# converter.net
KiCad netlist of a schematic drawn in EAGLE
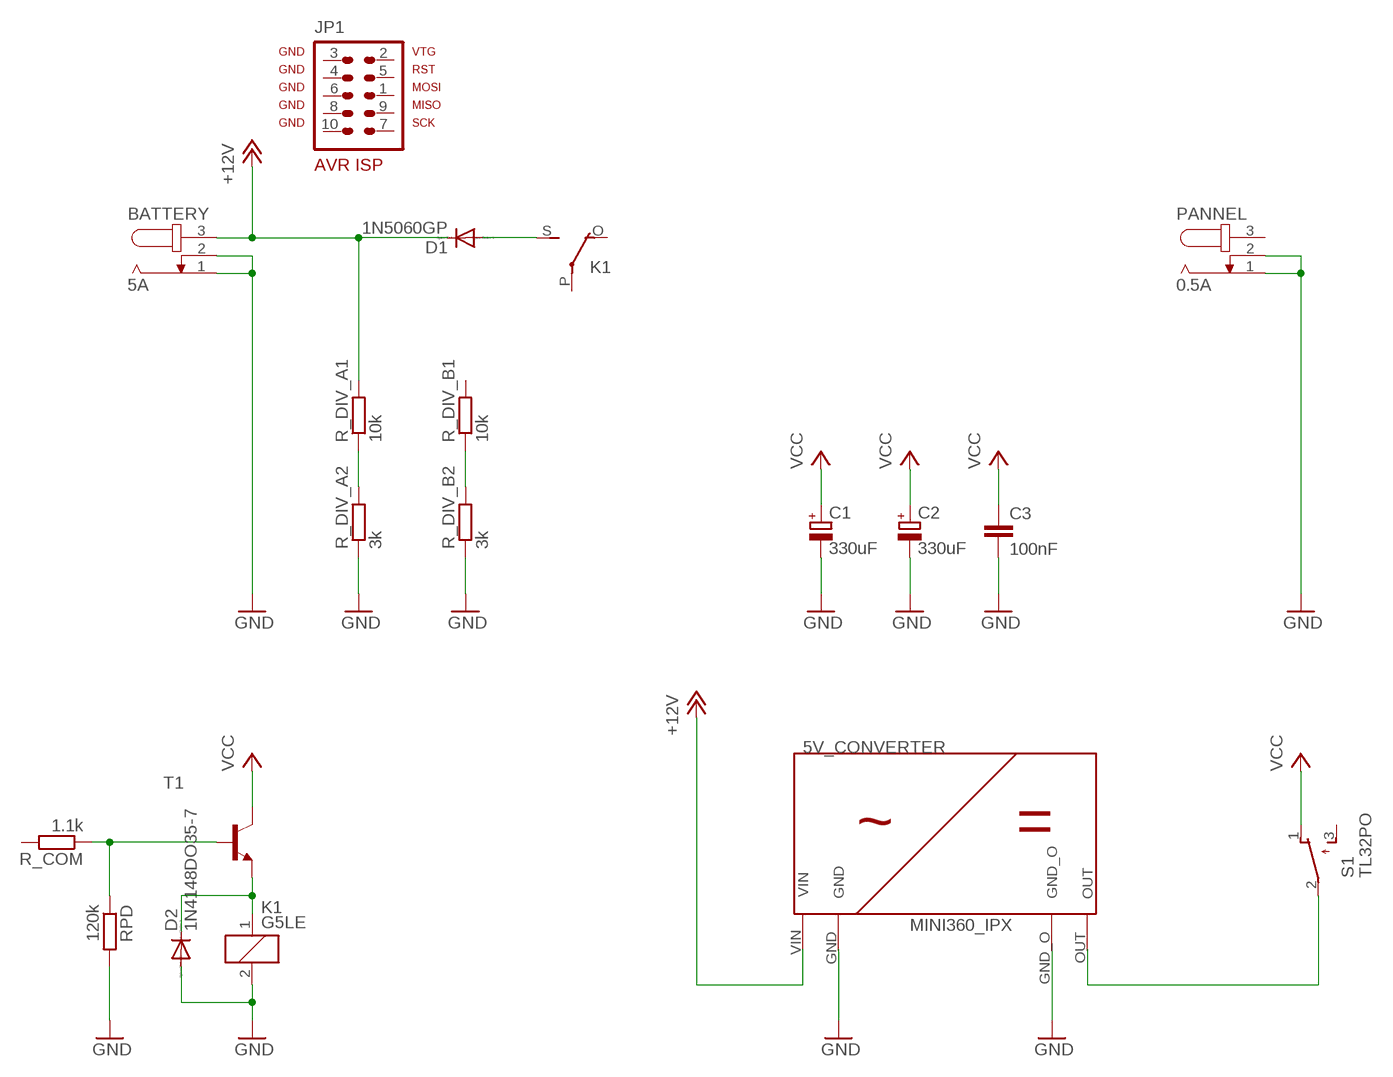
[diagram p0: schematic, sheet 1]

(export (version "E")
  (design (tool "Eeschema 10.0.6"))
  (components
    (comp (ref "5V_CONVERTER")
      (value "MINI360_IPX")
      (footprint "eagle-import:MINI360_IPX")
      (libsource (lib "eagle-import") (part "MINI360_IPX"))
    )
    (comp (ref "BATTERY")
      (value "5A")
      (footprint "eagle-import:SPC4077")
      (libsource (lib "eagle-import") (part "JACK-PLUG0"))
    )
    (comp (ref "C1")
      (value "330uF")
      (footprint "eagle-import:E2,5-7")
      (libsource (lib "eagle-import") (part "CPOL-EUE2.5-7"))
    )
    (comp (ref "C2")
      (value "330uF")
      (footprint "eagle-import:E2,5-7")
      (libsource (lib "eagle-import") (part "CPOL-EUE2.5-7"))
    )
    (comp (ref "C3")
      (value "100nF")
      (footprint "eagle-import:C025-030X050")
      (libsource (lib "eagle-import") (part "C-EU025-030X050"))
    )
    (comp (ref "D1")
      (value "1N5060GP")
      (footprint "eagle-import:DO15-12")
      (libsource (lib "eagle-import") (part "1N5060GP"))
    )
    (comp (ref "D2")
      (value "1N4148DO35-7")
      (footprint "eagle-import:DO35-7")
      (libsource (lib "eagle-import") (part "1N4148DO35-7"))
    )
    (comp (ref "JP1")
      (value "AVR-ISP-10")
      (footprint "eagle-import:AVR-ISP-10")
      (libsource (lib "eagle-import") (part "AVR-ISP-10"))
    )
    (comp (ref "K1")
      (value "G5LE")
      (footprint "eagle-import:G5LE")
      (libsource (lib "eagle-import") (part "G5LE"))
    )
    (comp (ref "PANNEL")
      (value "0.5A")
      (footprint "eagle-import:SPC4077")
      (libsource (lib "eagle-import") (part "JACK-PLUG0"))
    )
    (comp (ref "RPD")
      (value "120k")
      (footprint "eagle-import:0207_10")
      (libsource (lib "eagle-import") (part "R-EU_0207/10"))
    )
    (comp (ref "R_COM")
      (value "1.1k")
      (footprint "eagle-import:0207_10")
      (libsource (lib "eagle-import") (part "R-EU_0207/10"))
    )
    (comp (ref "R_DIV_A1")
      (value "10k")
      (footprint "eagle-import:0207_10")
      (libsource (lib "eagle-import") (part "R-EU_0207/10"))
    )
    (comp (ref "R_DIV_A2")
      (value "3k")
      (footprint "eagle-import:0207_10")
      (libsource (lib "eagle-import") (part "R-EU_0207/10"))
    )
    (comp (ref "R_DIV_B1")
      (value "10k")
      (footprint "eagle-import:0207_10")
      (libsource (lib "eagle-import") (part "R-EU_0207/10"))
    )
    (comp (ref "R_DIV_B2")
      (value "3k")
      (footprint "eagle-import:0207_10")
      (libsource (lib "eagle-import") (part "R-EU_0207/10"))
    )
    (comp (ref "S1")
      (value "TL32PO")
      (footprint "eagle-import:TL3XPO")
      (libsource (lib "eagle-import") (part "TL32PO"))
    )
    (comp (ref "T1")
      (value "2N5551-NPN-TO92-EBC")
      (footprint "eagle-import:TO92-EBC")
      (libsource (lib "eagle-import") (part "-NPN-TO92-EBC2N5551"))
    )
  )
  (nets
    (net (code "1") (name "+12V") (class "Default")
      (node (ref "5V_CONVERTER") (pin "VIN") (pinfunction "VIN_VIN") (pintype "bidirectional"))
      (node (ref "BATTERY") (pin "3") (pinfunction "3_3") (pintype "passive"))
      (node (ref "D1") (pin "C") (pinfunction "C_C") (pintype "passive"))
      (node (ref "R_DIV_A1") (pin "2") (pinfunction "2_2") (pintype "passive"))
    )
    (net (code "2") (name "GND") (class "Default")
      (node (ref "BATTERY") (pin "1") (pinfunction "1_1") (pintype "passive"))
      (node (ref "BATTERY") (pin "2") (pinfunction "2_2") (pintype "passive"))
      (node (ref "C1") (pin "-") (pinfunction "-_-") (pintype "passive"))
      (node (ref "C2") (pin "-") (pinfunction "-_-") (pintype "passive"))
      (node (ref "C3") (pin "2") (pinfunction "2_2") (pintype "passive"))
      (node (ref "D2") (pin "A") (pinfunction "A_A") (pintype "passive"))
      (node (ref "K1") (pin "2") (pinfunction "2_2") (pintype "passive"))
      (node (ref "PANNEL") (pin "1") (pinfunction "1_1") (pintype "passive"))
      (node (ref "PANNEL") (pin "2") (pinfunction "2_2") (pintype "passive"))
      (node (ref "RPD") (pin "2") (pinfunction "2_2") (pintype "passive"))
      (node (ref "R_DIV_A2") (pin "1") (pinfunction "1_1") (pintype "passive"))
      (node (ref "R_DIV_B2") (pin "1") (pinfunction "1_1") (pintype "passive"))
    )
    (net (code "3") (name "Net-(D1-PadA)") (class "Default")
      (node (ref "D1") (pin "A") (pinfunction "A_A") (pintype "passive"))
      (node (ref "K1") (pin "S") (pinfunction "S_S") (pintype "passive"))
    )
    (net (code "4") (name "Net-(D2-PadC)") (class "Default")
      (node (ref "D2") (pin "C") (pinfunction "C_C") (pintype "passive"))
      (node (ref "K1") (pin "1") (pinfunction "1_1") (pintype "passive"))
      (node (ref "T1") (pin "E") (pinfunction "E_E") (pintype "passive"))
    )
    (net (code "5") (name "Net-(RPD-Pad1)") (class "Default")
      (node (ref "RPD") (pin "1") (pinfunction "1_1") (pintype "passive"))
      (node (ref "R_COM") (pin "1") (pinfunction "1_1") (pintype "passive"))
      (node (ref "T1") (pin "B") (pinfunction "B_B") (pintype "passive"))
    )
    (net (code "6") (name "Net-(R_DIV_A1-Pad1)") (class "Default")
      (node (ref "R_DIV_A1") (pin "1") (pinfunction "1_1") (pintype "passive"))
      (node (ref "R_DIV_A2") (pin "2") (pinfunction "2_2") (pintype "passive"))
    )
    (net (code "7") (name "Net-(R_DIV_B1-Pad1)") (class "Default")
      (node (ref "R_DIV_B1") (pin "1") (pinfunction "1_1") (pintype "passive"))
      (node (ref "R_DIV_B2") (pin "2") (pinfunction "2_2") (pintype "passive"))
    )
    (net (code "8") (name "VCC") (class "Default")
      (node (ref "C1") (pin "+") (pinfunction "+_+") (pintype "passive"))
      (node (ref "C2") (pin "+") (pinfunction "+_+") (pintype "passive"))
      (node (ref "C3") (pin "1") (pinfunction "1_1") (pintype "passive"))
      (node (ref "S1") (pin "1") (pinfunction "O_1") (pintype "passive"))
      (node (ref "T1") (pin "C") (pinfunction "C_C") (pintype "passive"))
    )
    (net (code "9") (name "unconnected-(5V_CONVERTER-PadGND)") (class "Default")
      (node (ref "5V_CONVERTER") (pin "GND") (pinfunction "GND_GND") (pintype "bidirectional"))
    )
    (net (code "10") (name "unconnected-(5V_CONVERTER-PadGND_O)") (class "Default")
      (node (ref "5V_CONVERTER") (pin "GND_O") (pinfunction "GND_O_GND_O") (pintype "bidirectional"))
    )
    (net (code "11") (name "unconnected-(5V_CONVERTER-PadOUT)") (class "Default")
      (node (ref "5V_CONVERTER") (pin "OUT") (pinfunction "OUT_OUT") (pintype "bidirectional"))
    )
    (net (code "12") (name "unconnected-(JP1-Pad1)") (class "Default")
      (node (ref "JP1") (pin "1") (pinfunction "1_1") (pintype "passive"))
    )
    (net (code "13") (name "unconnected-(JP1-Pad2)") (class "Default")
      (node (ref "JP1") (pin "2") (pinfunction "2_2") (pintype "passive"))
    )
    (net (code "14") (name "unconnected-(JP1-Pad3)") (class "Default")
      (node (ref "JP1") (pin "3") (pinfunction "3_3") (pintype "passive"))
    )
    (net (code "15") (name "unconnected-(JP1-Pad4)") (class "Default")
      (node (ref "JP1") (pin "4") (pinfunction "4_4") (pintype "passive"))
    )
    (net (code "16") (name "unconnected-(JP1-Pad5)") (class "Default")
      (node (ref "JP1") (pin "5") (pinfunction "5_5") (pintype "passive"))
    )
    (net (code "17") (name "unconnected-(JP1-Pad6)") (class "Default")
      (node (ref "JP1") (pin "6") (pinfunction "6_6") (pintype "passive"))
    )
    (net (code "18") (name "unconnected-(JP1-Pad7)") (class "Default")
      (node (ref "JP1") (pin "7") (pinfunction "7_7") (pintype "passive"))
    )
    (net (code "19") (name "unconnected-(JP1-Pad8)") (class "Default")
      (node (ref "JP1") (pin "8") (pinfunction "8_8") (pintype "passive"))
    )
    (net (code "20") (name "unconnected-(JP1-Pad9)") (class "Default")
      (node (ref "JP1") (pin "9") (pinfunction "9_9") (pintype "passive"))
    )
    (net (code "21") (name "unconnected-(JP1-Pad10)") (class "Default")
      (node (ref "JP1") (pin "10") (pinfunction "10_10") (pintype "passive"))
    )
    (net (code "22") (name "unconnected-(K1-PadO)") (class "Default")
      (node (ref "K1") (pin "O") (pinfunction "O_O") (pintype "passive"))
    )
    (net (code "23") (name "unconnected-(K1-PadP)") (class "Default")
      (node (ref "K1") (pin "P") (pinfunction "P_P") (pintype "passive"))
    )
    (net (code "24") (name "unconnected-(PANNEL-Pad3)") (class "Default")
      (node (ref "PANNEL") (pin "3") (pinfunction "3_3") (pintype "passive"))
    )
    (net (code "25") (name "unconnected-(R_COM-Pad2)") (class "Default")
      (node (ref "R_COM") (pin "2") (pinfunction "2_2") (pintype "passive"))
    )
    (net (code "26") (name "unconnected-(R_DIV_B1-Pad2)") (class "Default")
      (node (ref "R_DIV_B1") (pin "2") (pinfunction "2_2") (pintype "passive"))
    )
    (net (code "27") (name "unconnected-(S1-P-Pad2)") (class "Default")
      (node (ref "S1") (pin "2") (pinfunction "P_2") (pintype "passive"))
    )
    (net (code "28") (name "unconnected-(S1-S-Pad3)") (class "Default")
      (node (ref "S1") (pin "3") (pinfunction "S_3") (pintype "passive"))
    )
  )
)
